# leistung.net
KiCad netlist of a schematic drawn in EAGLE
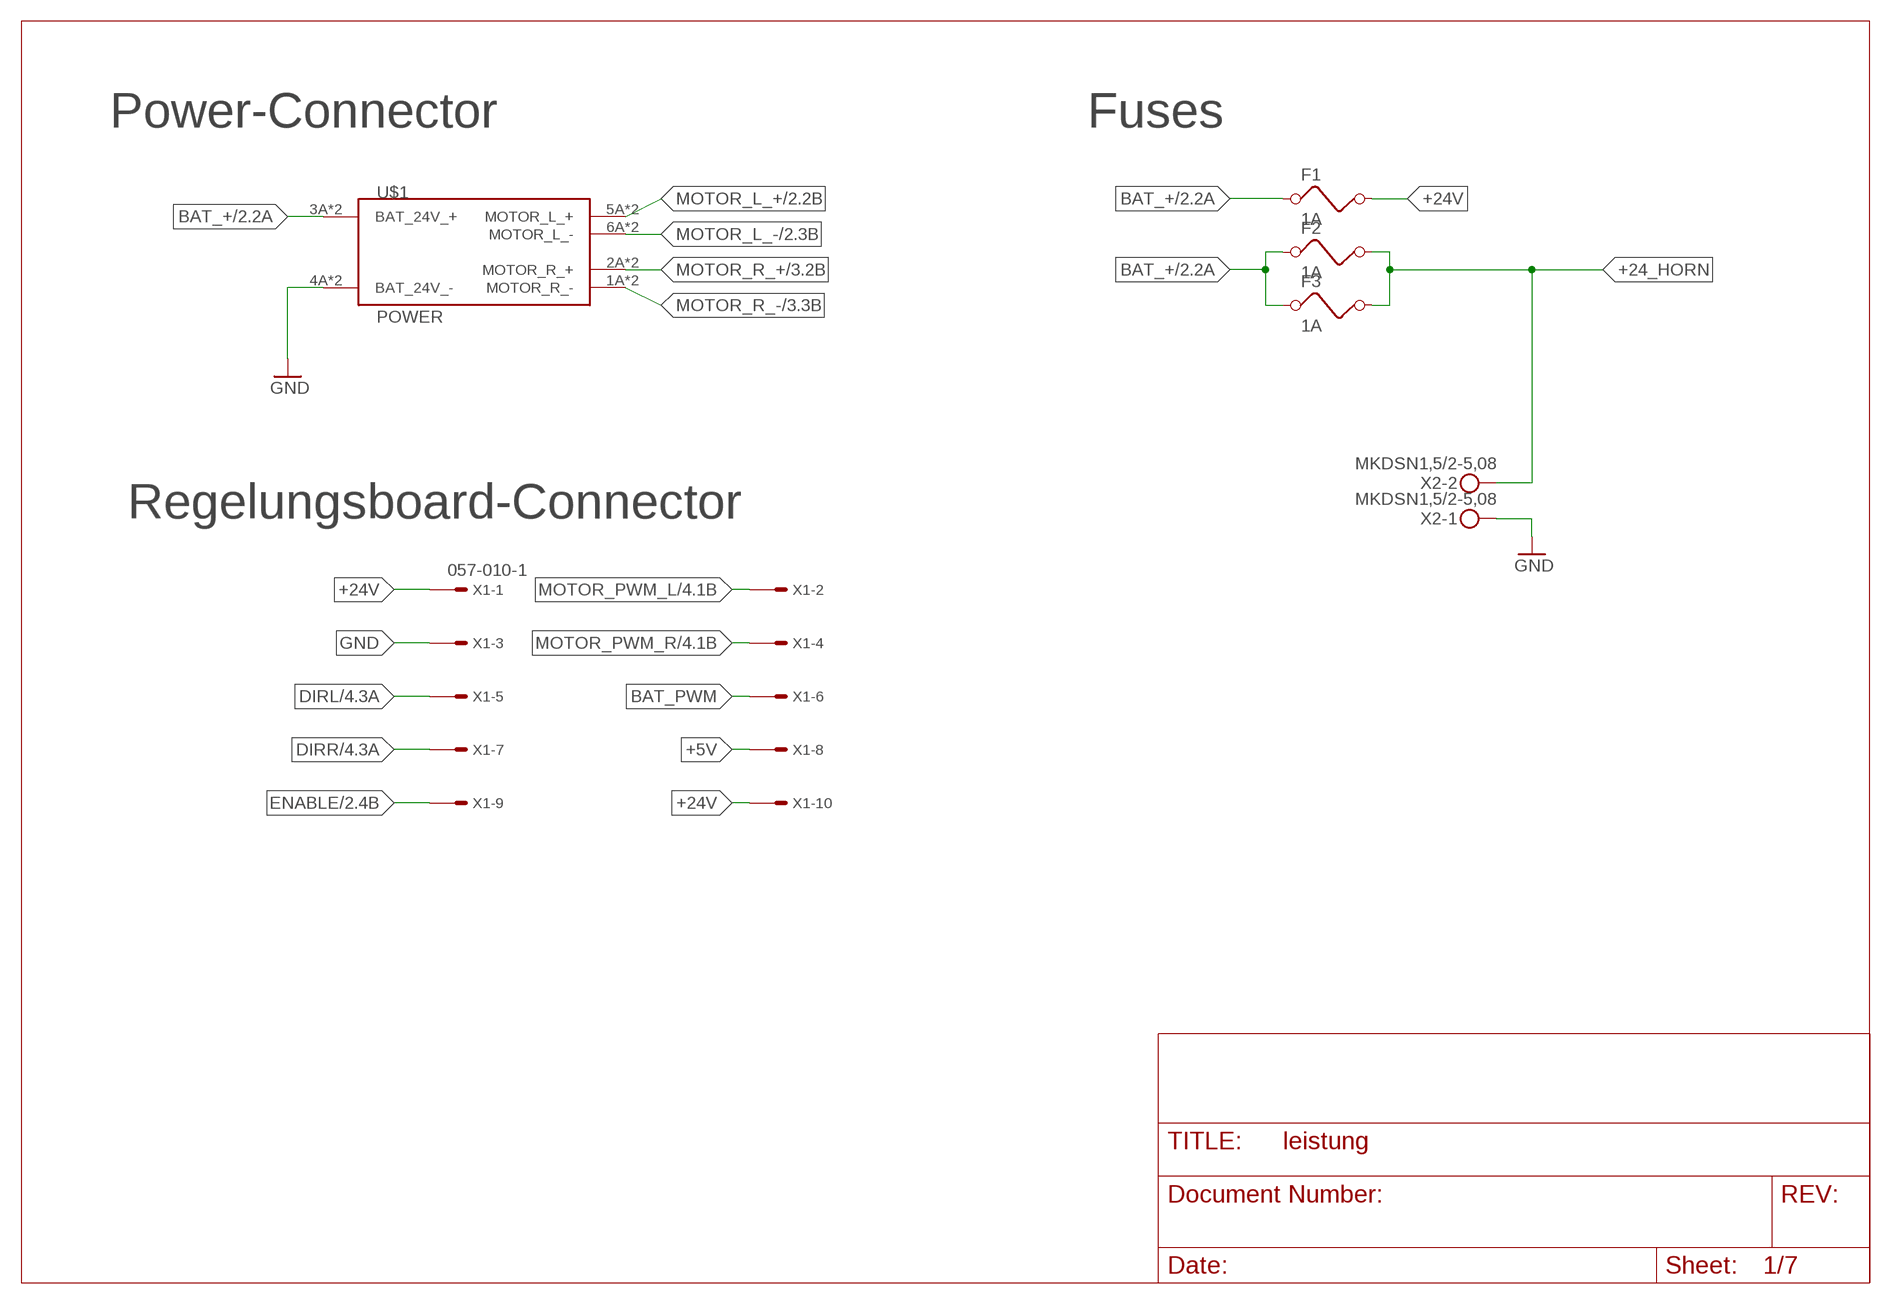
[diagram p0: schematic, sheet 1]
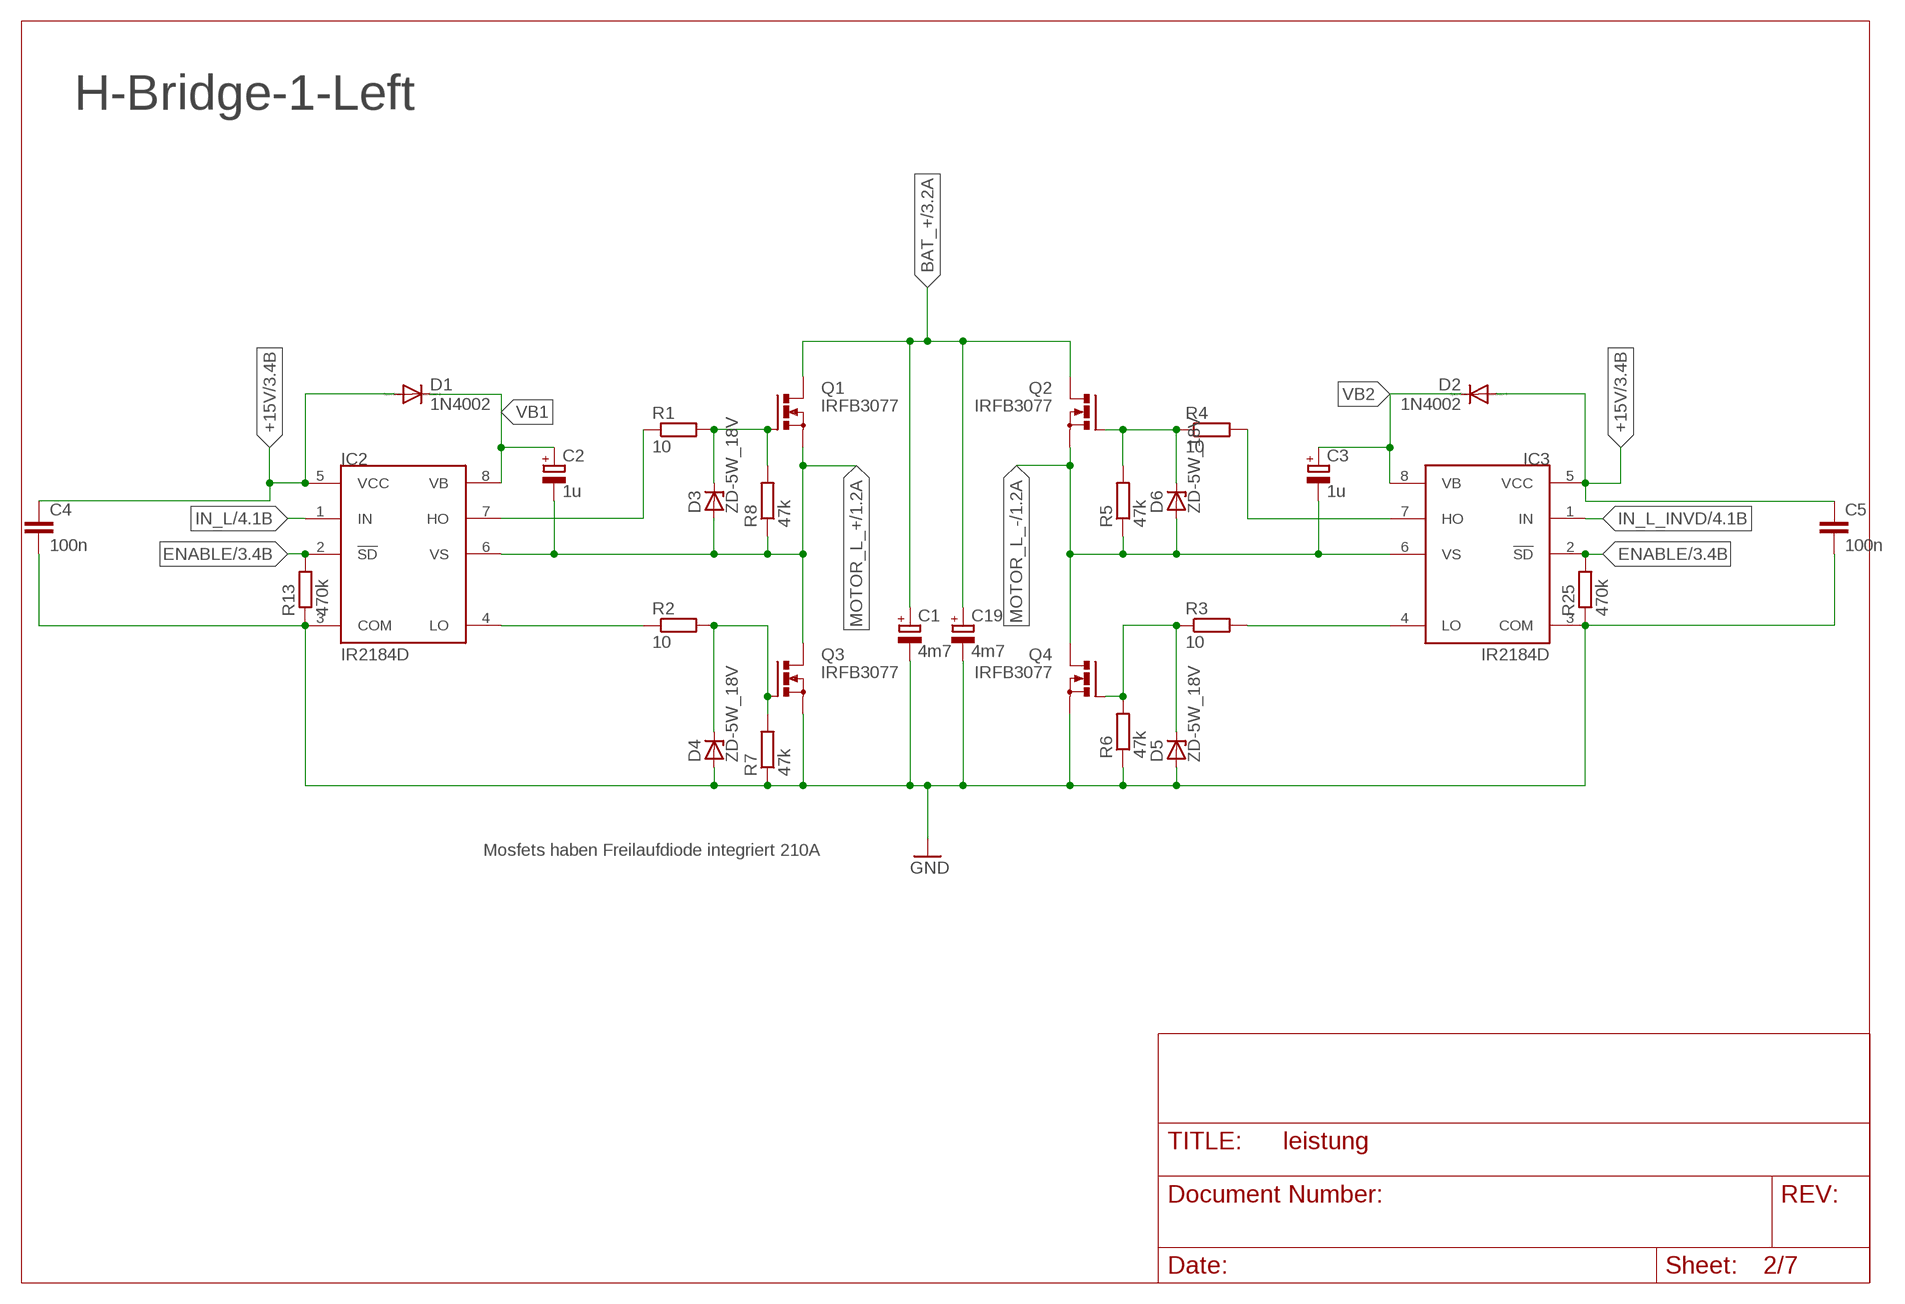
[diagram p1: schematic, sheet 2]
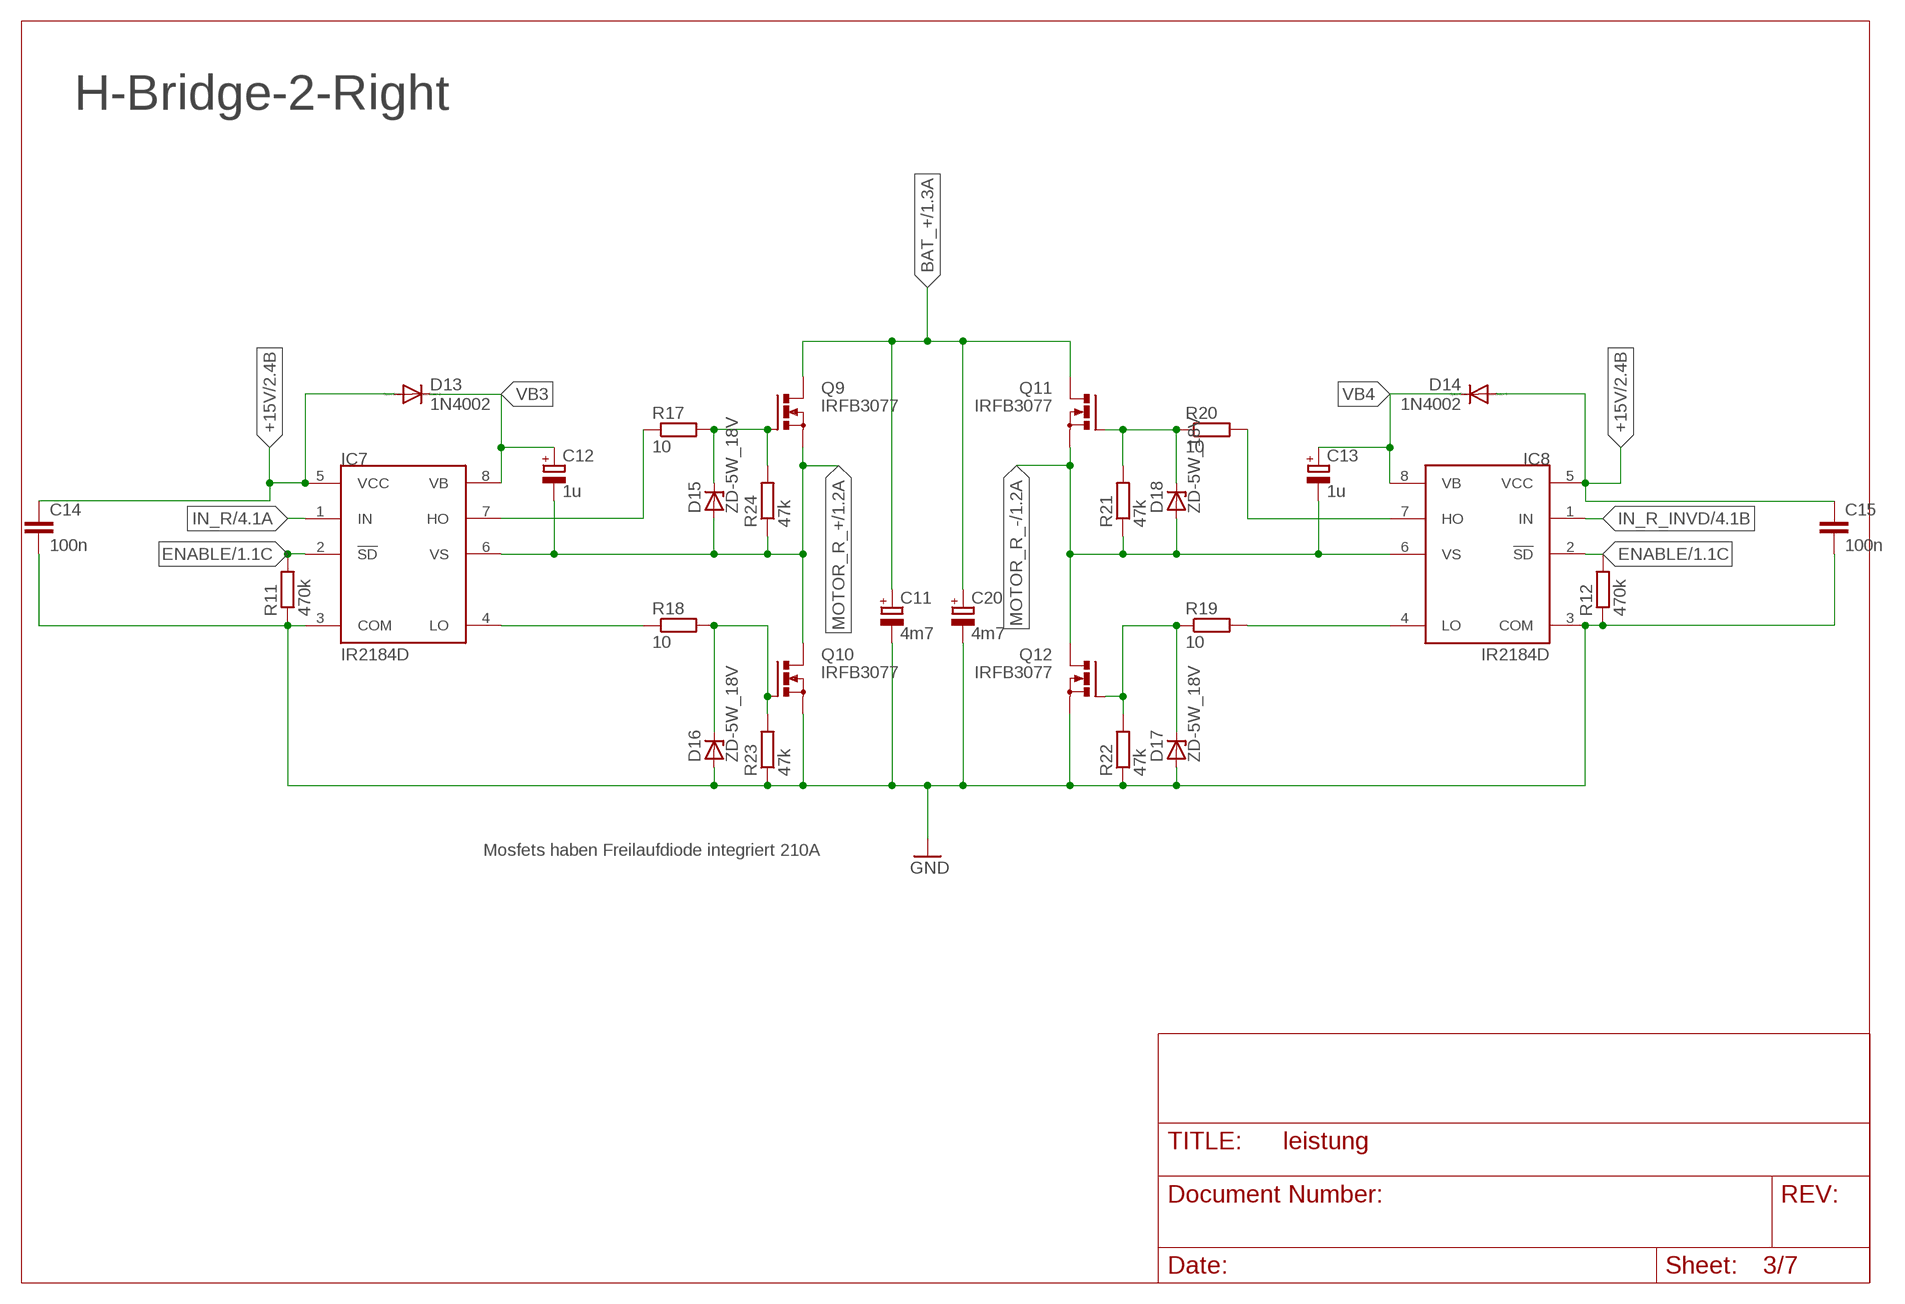
[diagram p2: schematic, sheet 3]
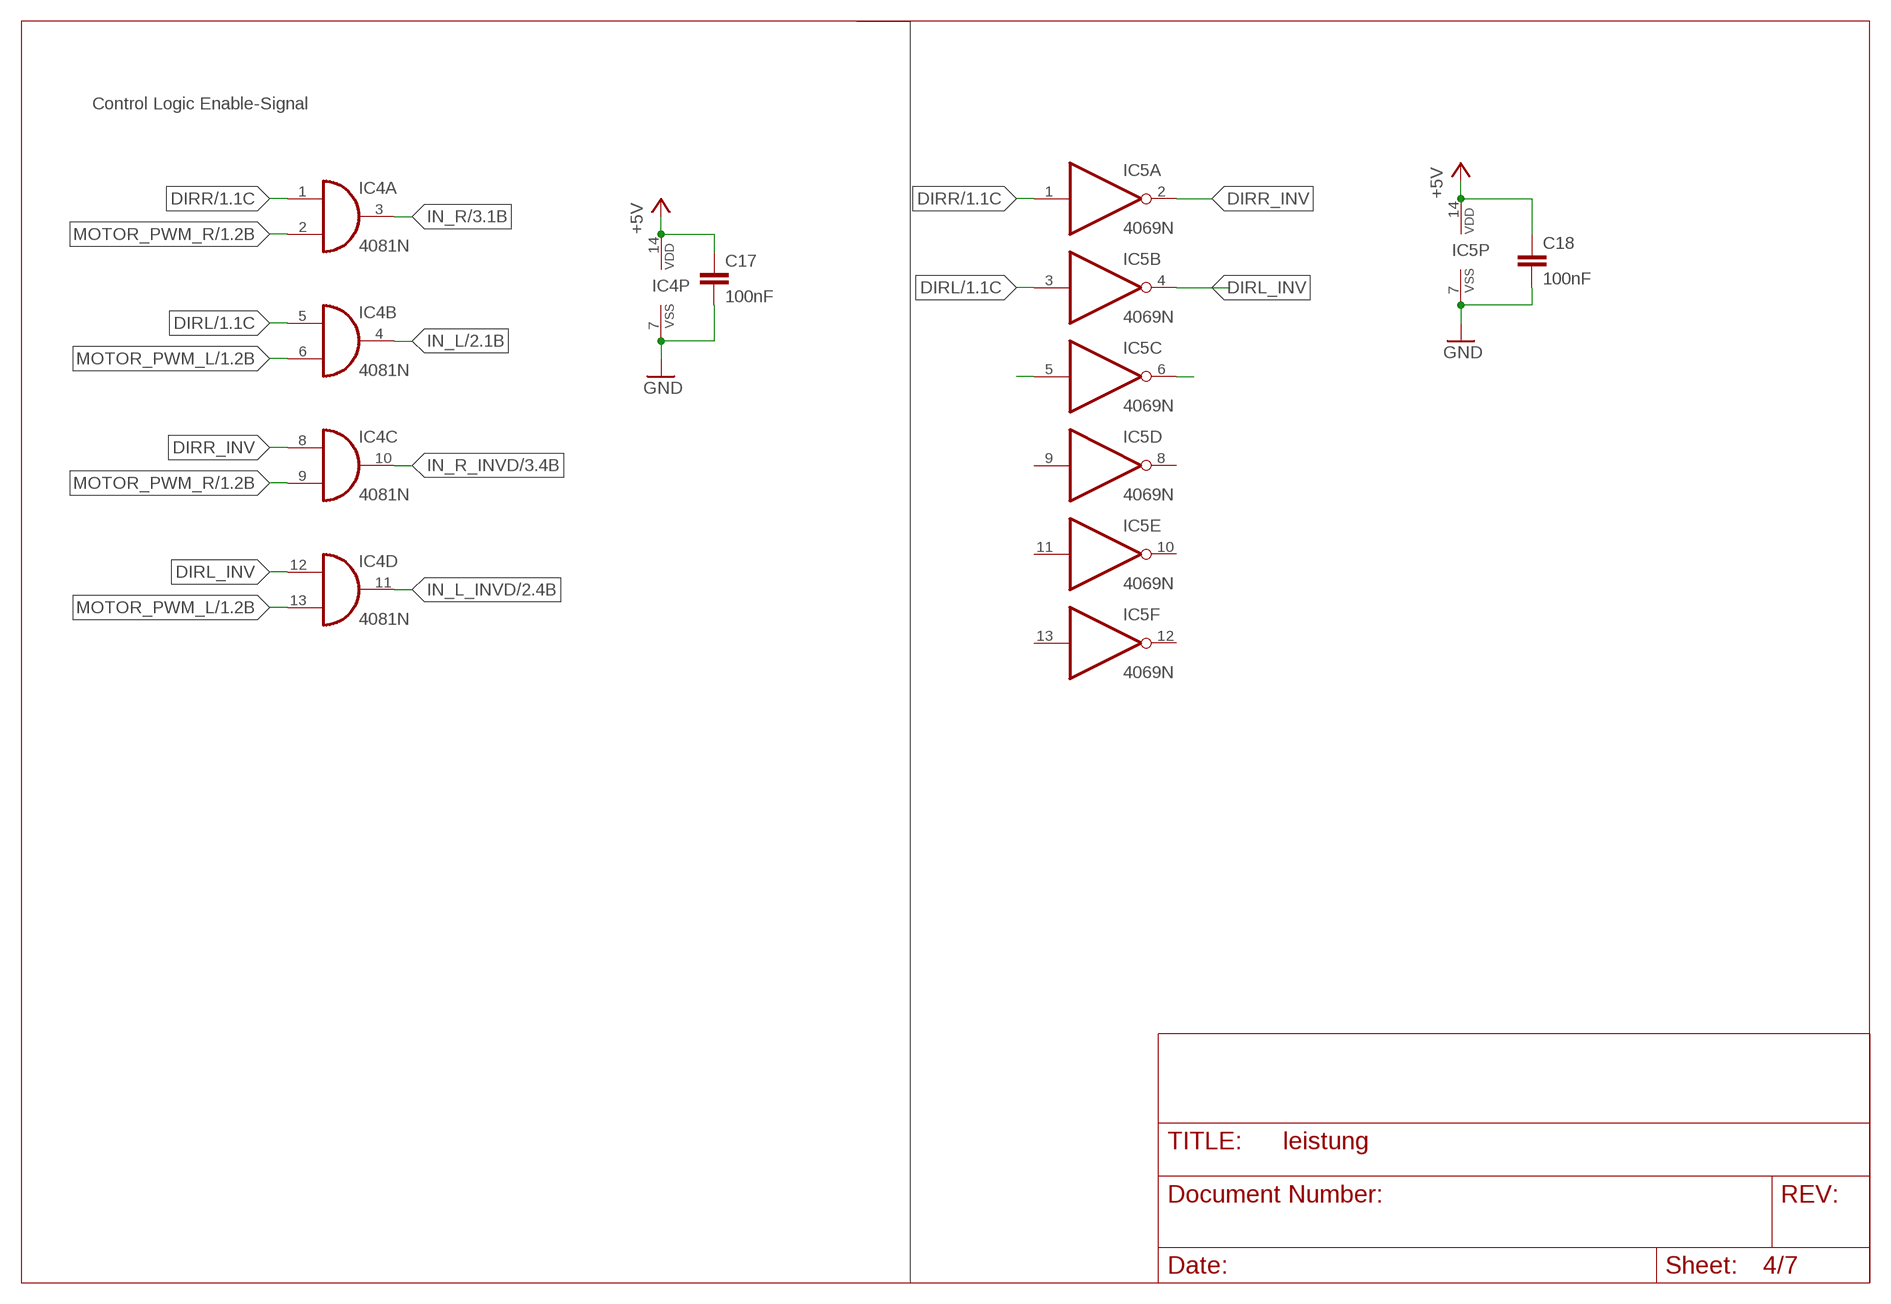
[diagram p3: schematic, sheet 4]
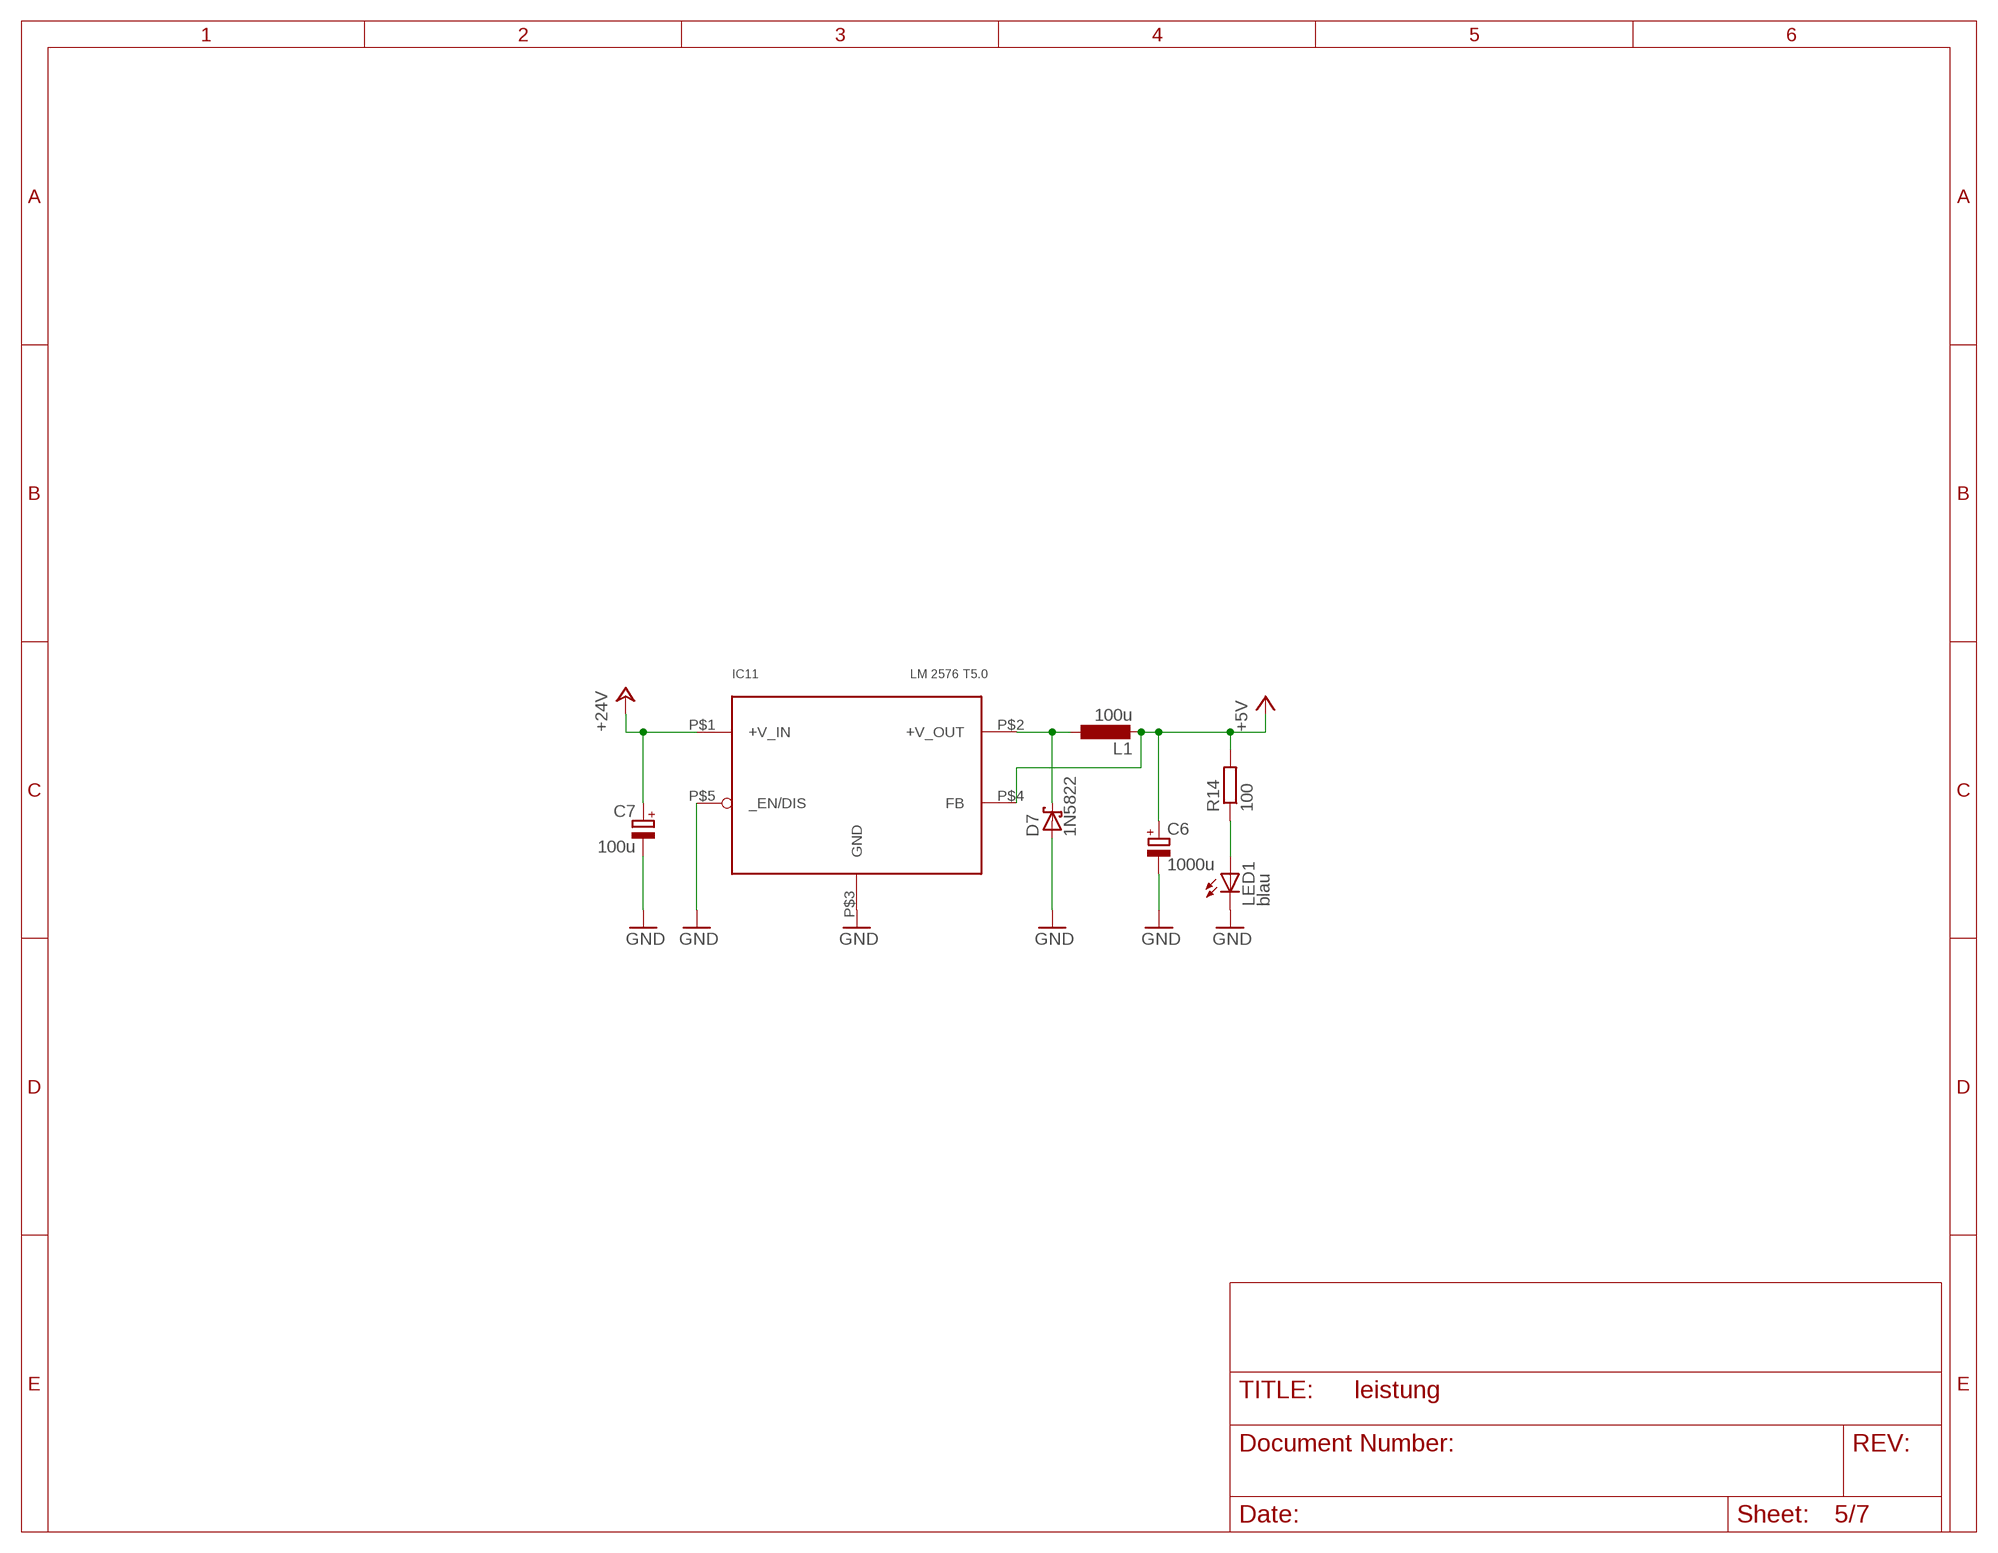
[diagram p4: schematic, sheet 5]
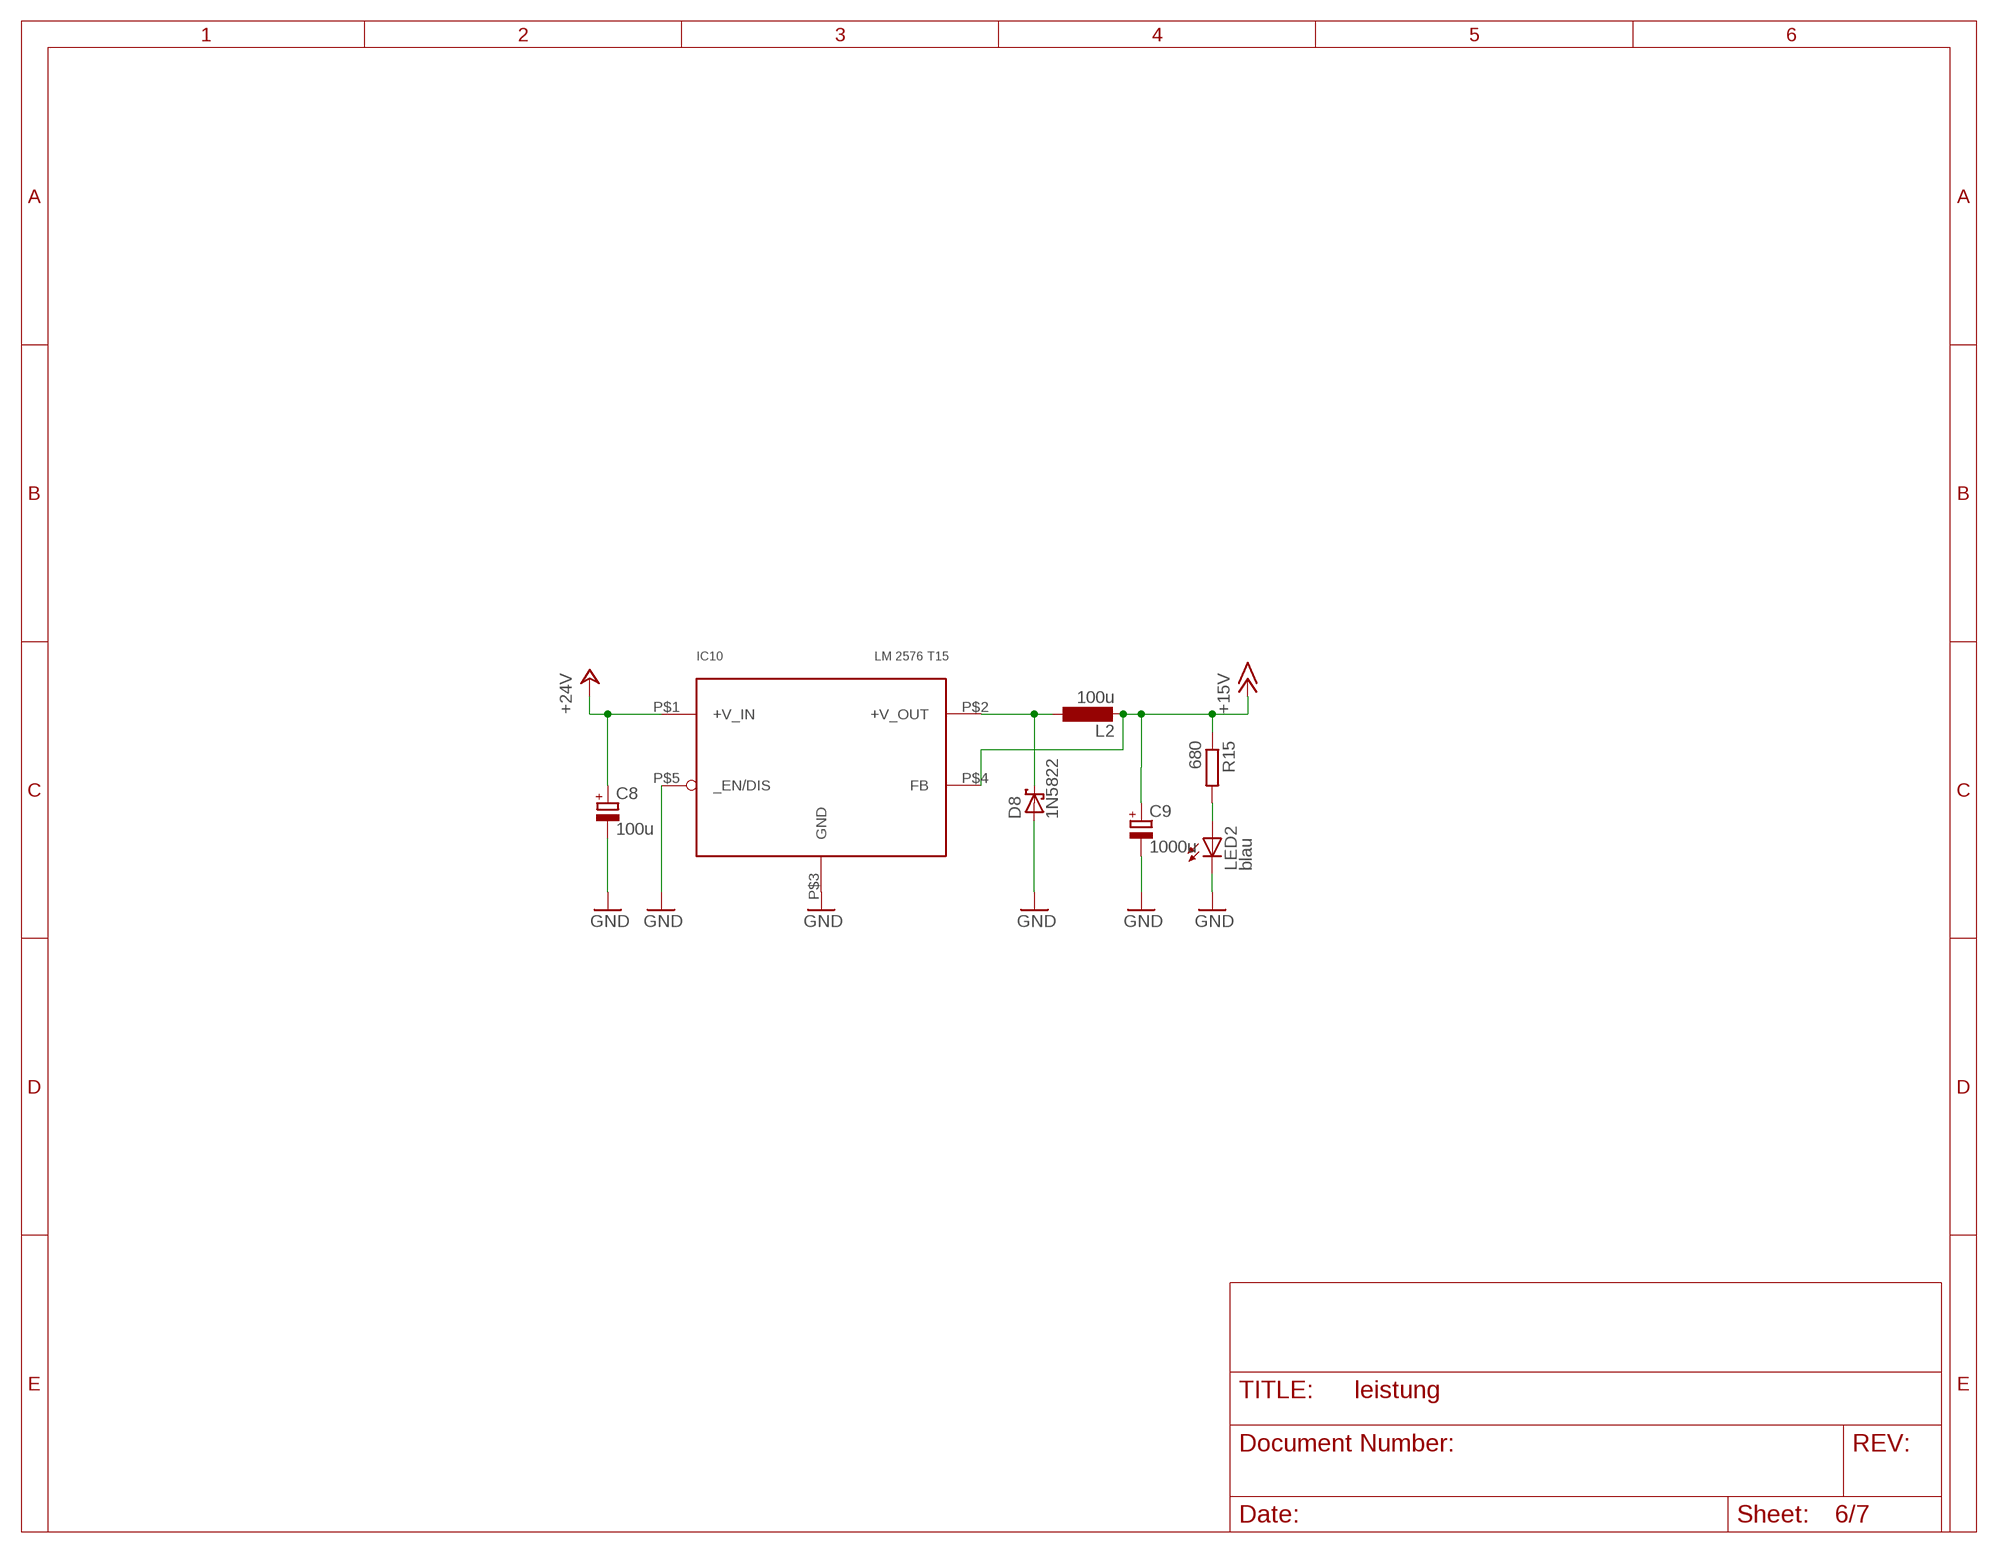
[diagram p5: schematic, sheet 6]
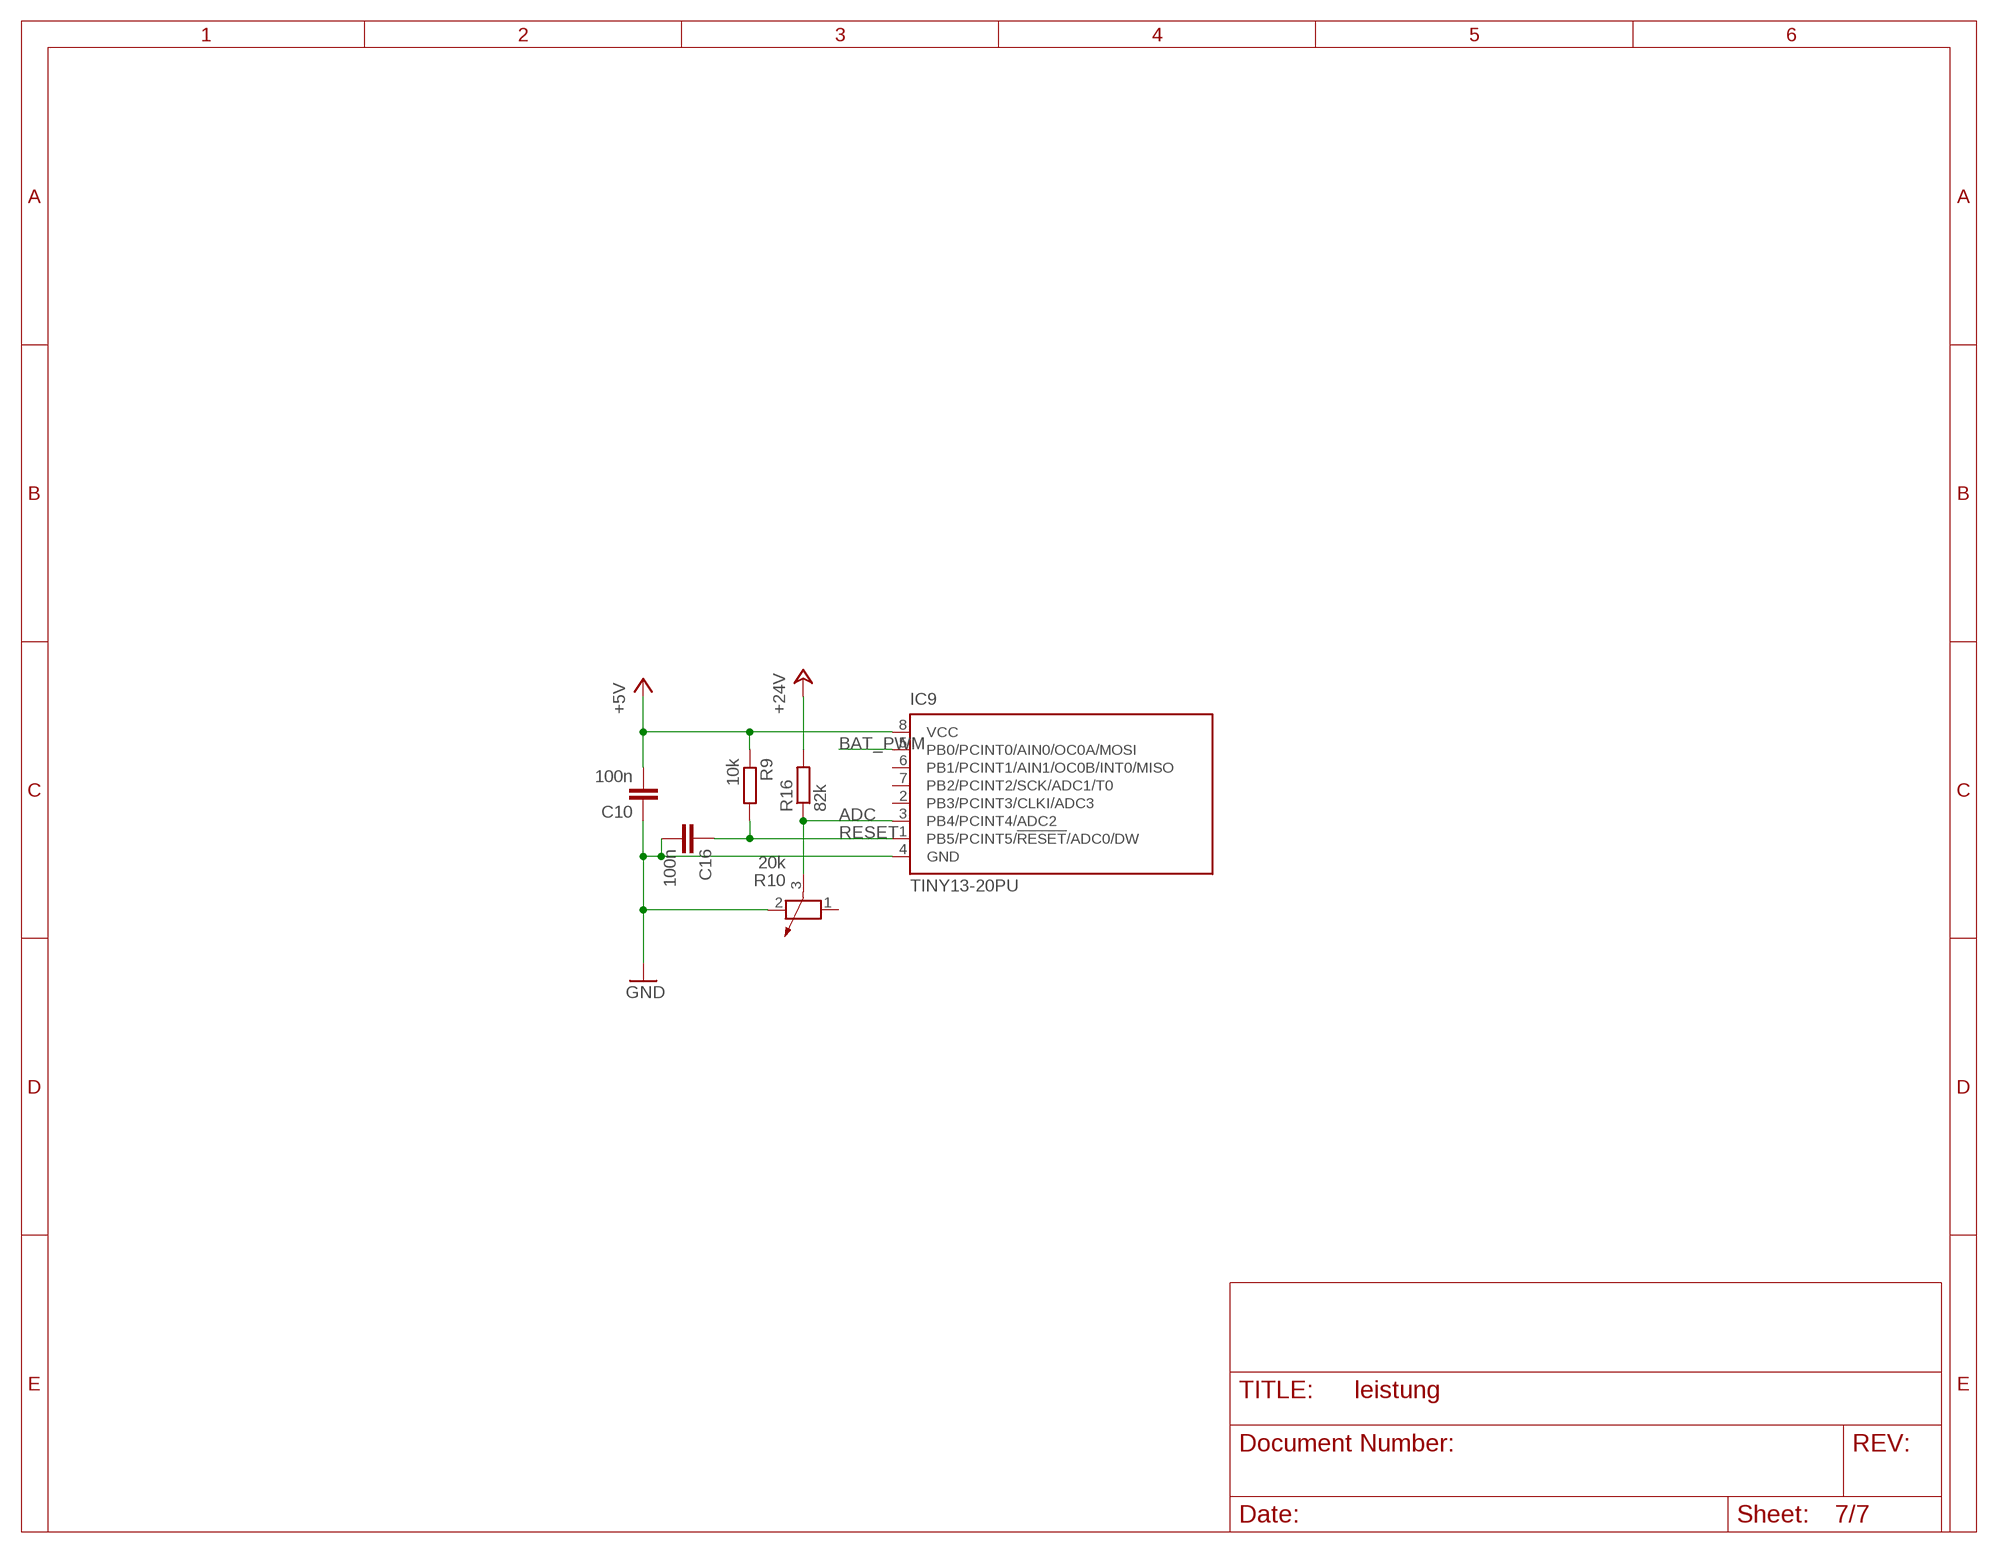
[diagram p6: schematic, sheet 7]

(export (version "E")
  (design (tool "Eeschema 10.0.6"))
  (components
    (comp (ref "F1")
      (value "1A")
      (footprint "eagle-import:FUSE")
      (libsource (lib "eagle-import") (part "FUSE"))
    )
    (comp (ref "F2")
      (value "1A")
      (footprint "eagle-import:FUSE")
      (libsource (lib "eagle-import") (part "FUSE"))
    )
    (comp (ref "F3")
      (value "1A")
      (footprint "eagle-import:FUSE")
      (libsource (lib "eagle-import") (part "FUSE"))
    )
    (comp (ref "U$1")
      (value "POWER")
      (footprint "eagle-import:CON_POWER")
      (libsource (lib "eagle-import") (part "POWER"))
    )
    (comp (ref "X1")
      (value "057-010-1")
      (footprint "eagle-import:057-010-1")
      (libsource (lib "eagle-import") (part "057-010-1"))
    )
    (comp (ref "X2")
      (value "MKDSN1,5/2-5,08")
      (footprint "eagle-import:MKDSN1,5_2-5,08")
      (libsource (lib "eagle-import") (part "MKDSN1,5/2-5,08"))
    )
    (comp (ref "C8")
      (value "100u")
      (footprint "eagle-import:E2,5-7")
      (libsource (lib "eagle-import") (part "CPOL-EUE2.5-7"))
    )
    (comp (ref "C9")
      (value "1000u")
      (footprint "eagle-import:E5-13")
      (libsource (lib "eagle-import") (part "rcl_334_CPOL-EUE5-13"))
    )
    (comp (ref "D8")
      (value "1N5822")
      (footprint "eagle-import:CB429-15")
      (libsource (lib "eagle-import") (part "SCHOTTKY-DIODECB429-15"))
    )
    (comp (ref "IC10")
      (value "LM 2576 T15")
      (footprint "eagle-import:TO220-5_STAGGERED")
      (libsource (lib "eagle-import") (part "LM2576-T05D"))
    )
    (comp (ref "L2")
      (value "100u")
      (footprint "eagle-import:0207_10")
      (libsource (lib "eagle-import") (part "L-EU0207/10"))
    )
    (comp (ref "LED2")
      (value "blau")
      (footprint "eagle-import:LED3MM")
      (libsource (lib "eagle-import") (part "LED3MM"))
    )
    (comp (ref "R15")
      (value "680")
      (footprint "eagle-import:0207_10")
      (libsource (lib "eagle-import") (part "R-EU_0207/10"))
    )
    (comp (ref "C1")
      (value "4m7")
      (footprint "eagle-import:E7,5-18")
      (libsource (lib "eagle-import") (part "rcl_334_CPOL-EUE7.5-18"))
    )
    (comp (ref "C2")
      (value "1u")
      (footprint "eagle-import:E2,5-5")
      (libsource (lib "eagle-import") (part "rcl_334_CPOL-EUE2.5-5"))
    )
    (comp (ref "C3")
      (value "1u")
      (footprint "eagle-import:E2,5-5")
      (libsource (lib "eagle-import") (part "rcl_334_CPOL-EUE2.5-5"))
    )
    (comp (ref "C4")
      (value "100n")
      (footprint "eagle-import:C025-025X050")
      (libsource (lib "eagle-import") (part "rcl_334_C-EU025-025X050"))
    )
    (comp (ref "C5")
      (value "100n")
      (footprint "eagle-import:C025-025X050")
      (libsource (lib "eagle-import") (part "rcl_334_C-EU025-025X050"))
    )
    (comp (ref "C19")
      (value "4m7")
      (footprint "eagle-import:E7,5-18")
      (libsource (lib "eagle-import") (part "rcl_334_CPOL-EUE7.5-18"))
    )
    (comp (ref "D1")
      (value "1N4002")
      (footprint "eagle-import:DO41-10")
      (libsource (lib "eagle-import") (part "1N4004"))
    )
    (comp (ref "D2")
      (value "1N4002")
      (footprint "eagle-import:DO41-10")
      (libsource (lib "eagle-import") (part "1N4004"))
    )
    (comp (ref "D3")
      (value "ZD-5W_18V")
      (footprint "eagle-import:ZDIO-10")
      (libsource (lib "eagle-import") (part "ZENER-DIODEZD-10"))
    )
    (comp (ref "D4")
      (value "ZD-5W_18V")
      (footprint "eagle-import:ZDIO-10")
      (libsource (lib "eagle-import") (part "ZENER-DIODEZD-10"))
    )
    (comp (ref "D5")
      (value "ZD-5W_18V")
      (footprint "eagle-import:ZDIO-10")
      (libsource (lib "eagle-import") (part "ZENER-DIODEZD-10"))
    )
    (comp (ref "D6")
      (value "ZD-5W_18V")
      (footprint "eagle-import:ZDIO-10")
      (libsource (lib "eagle-import") (part "ZENER-DIODEZD-10"))
    )
    (comp (ref "IC2")
      (value "IR2184D")
      (footprint "eagle-import:DIL08")
      (libsource (lib "eagle-import") (part "IR2184D"))
    )
    (comp (ref "IC3")
      (value "IR2184D")
      (footprint "eagle-import:DIL08")
      (libsource (lib "eagle-import") (part "IR2184D"))
    )
    (comp (ref "Q1")
      (value "IRFB3077")
      (footprint "eagle-import:TO220BV")
      (libsource (lib "eagle-import") (part "PMOSFET_NTO220BV"))
    )
    (comp (ref "Q2")
      (value "IRFB3077")
      (footprint "eagle-import:TO220BV")
      (libsource (lib "eagle-import") (part "PMOSFET_NTO220BV"))
    )
    (comp (ref "Q3")
      (value "IRFB3077")
      (footprint "eagle-import:TO220BV")
      (libsource (lib "eagle-import") (part "PMOSFET_NTO220BV"))
    )
    (comp (ref "Q4")
      (value "IRFB3077")
      (footprint "eagle-import:TO220BV")
      (libsource (lib "eagle-import") (part "PMOSFET_NTO220BV"))
    )
    (comp (ref "R1")
      (value "10")
      (footprint "eagle-import:0207_7")
      (libsource (lib "eagle-import") (part "rcl_334_R-EU_0207/7"))
    )
    (comp (ref "R2")
      (value "10")
      (footprint "eagle-import:0207_7")
      (libsource (lib "eagle-import") (part "rcl_334_R-EU_0207/7"))
    )
    (comp (ref "R3")
      (value "10")
      (footprint "eagle-import:0207_7")
      (libsource (lib "eagle-import") (part "rcl_334_R-EU_0207/7"))
    )
    (comp (ref "R4")
      (value "10")
      (footprint "eagle-import:0207_7")
      (libsource (lib "eagle-import") (part "rcl_334_R-EU_0207/7"))
    )
    (comp (ref "R5")
      (value "47k")
      (footprint "eagle-import:0207_7")
      (libsource (lib "eagle-import") (part "rcl_334_R-EU_0207/7"))
    )
    (comp (ref "R6")
      (value "47k")
      (footprint "eagle-import:0207_7")
      (libsource (lib "eagle-import") (part "rcl_334_R-EU_0207/7"))
    )
    (comp (ref "R7")
      (value "47k")
      (footprint "eagle-import:0207_7")
      (libsource (lib "eagle-import") (part "rcl_334_R-EU_0207/7"))
    )
    (comp (ref "R8")
      (value "47k")
      (footprint "eagle-import:0207_7")
      (libsource (lib "eagle-import") (part "rcl_334_R-EU_0207/7"))
    )
    (comp (ref "R13")
      (value "470k")
      (footprint "eagle-import:0207_7")
      (libsource (lib "eagle-import") (part "rcl_334_R-EU_0207/7"))
    )
    (comp (ref "R25")
      (value "470k")
      (footprint "eagle-import:0207_7")
      (libsource (lib "eagle-import") (part "rcl_334_R-EU_0207/7"))
    )
    (comp (ref "C17")
      (value "100nF")
      (footprint "eagle-import:C025-025X050")
      (libsource (lib "eagle-import") (part "rcl_334_C-EU025-025X050"))
    )
    (comp (ref "C18")
      (value "100nF")
      (footprint "eagle-import:C025-025X050")
      (libsource (lib "eagle-import") (part "rcl_334_C-EU025-025X050"))
    )
    (comp (ref "IC4")
      (value "4081N")
      (footprint "eagle-import:DIL14")
      (libsource (lib "eagle-import") (part "4081N"))
    )
    (comp (ref "IC5")
      (value "4069N")
      (footprint "eagle-import:DIL14")
      (libsource (lib "eagle-import") (part "4069N"))
    )
    (comp (ref "C10")
      (value "100n")
      (footprint "eagle-import:C025-025X050")
      (libsource (lib "eagle-import") (part "C-EU025-025X050"))
    )
    (comp (ref "C16")
      (value "100n")
      (footprint "eagle-import:C025-025X050")
      (libsource (lib "eagle-import") (part "C-EU025-025X050"))
    )
    (comp (ref "IC9")
      (value "TINY13-20PU")
      (footprint "eagle-import:DIL08")
      (fields (field (name "MPN") "ATTINY13-20PU"))
      (libsource (lib "eagle-import") (part "TINY13PU-20"))
    )
    (comp (ref "R9")
      (value "10k")
      (footprint "eagle-import:0207_10")
      (libsource (lib "eagle-import") (part "R-EU_0207/10"))
    )
    (comp (ref "R10")
      (value "20k")
      (footprint "eagle-import:PT-10")
      (libsource (lib "eagle-import") (part "POTENTIOMETER_PT-10"))
    )
    (comp (ref "R16")
      (value "82k")
      (footprint "eagle-import:0207_10")
      (libsource (lib "eagle-import") (part "R-EU_0207/10"))
    )
    (comp (ref "C6")
      (value "1000u")
      (footprint "eagle-import:E5-13")
      (libsource (lib "eagle-import") (part "rcl_334_CPOL-EUE5-13"))
    )
    (comp (ref "C7")
      (value "100u")
      (footprint "eagle-import:E2,5-4R")
      (libsource (lib "eagle-import") (part "CPOL-EUE2.5-5V"))
    )
    (comp (ref "D7")
      (value "1N5822")
      (footprint "eagle-import:CB417-15")
      (libsource (lib "eagle-import") (part "SCHOTTKY-DIODECB417-15"))
    )
    (comp (ref "IC11")
      (value "LM 2576 T5.0")
      (footprint "eagle-import:TO220-5_STAGGERED")
      (libsource (lib "eagle-import") (part "LM2576-T05D"))
    )
    (comp (ref "L1")
      (value "100u")
      (footprint "eagle-import:0207_10")
      (libsource (lib "eagle-import") (part "L-EU0207/10"))
    )
    (comp (ref "LED1")
      (value "blau")
      (footprint "eagle-import:LED3MM")
      (libsource (lib "eagle-import") (part "LED3MM"))
    )
    (comp (ref "R14")
      (value "100")
      (footprint "eagle-import:0207_10")
      (libsource (lib "eagle-import") (part "R-EU_0207/10"))
    )
    (comp (ref "C11")
      (value "4m7")
      (footprint "eagle-import:E7,5-18")
      (libsource (lib "eagle-import") (part "rcl_334_CPOL-EUE7.5-18"))
    )
    (comp (ref "C12")
      (value "1u")
      (footprint "eagle-import:E2,5-5")
      (libsource (lib "eagle-import") (part "rcl_334_CPOL-EUE2.5-5"))
    )
    (comp (ref "C13")
      (value "1u")
      (footprint "eagle-import:E2,5-5")
      (libsource (lib "eagle-import") (part "rcl_334_CPOL-EUE2.5-5"))
    )
    (comp (ref "C14")
      (value "100n")
      (footprint "eagle-import:C025-025X050")
      (libsource (lib "eagle-import") (part "rcl_334_C-EU025-025X050"))
    )
    (comp (ref "C15")
      (value "100n")
      (footprint "eagle-import:C025-025X050")
      (libsource (lib "eagle-import") (part "rcl_334_C-EU025-025X050"))
    )
    (comp (ref "C20")
      (value "4m7")
      (footprint "eagle-import:E7,5-18")
      (libsource (lib "eagle-import") (part "rcl_334_CPOL-EUE7.5-18"))
    )
    (comp (ref "D13")
      (value "1N4002")
      (footprint "eagle-import:DO41-10")
      (libsource (lib "eagle-import") (part "1N4004"))
    )
    (comp (ref "D14")
      (value "1N4002")
      (footprint "eagle-import:DO41-10")
      (libsource (lib "eagle-import") (part "1N4004"))
    )
    (comp (ref "D15")
      (value "ZD-5W_18V")
      (footprint "eagle-import:ZDIO-10")
      (libsource (lib "eagle-import") (part "ZENER-DIODEZD-10"))
    )
    (comp (ref "D16")
      (value "ZD-5W_18V")
      (footprint "eagle-import:ZDIO-10")
      (libsource (lib "eagle-import") (part "ZENER-DIODEZD-10"))
    )
    (comp (ref "D17")
      (value "ZD-5W_18V")
      (footprint "eagle-import:ZDIO-10")
      (libsource (lib "eagle-import") (part "ZENER-DIODEZD-10"))
    )
    (comp (ref "D18")
      (value "ZD-5W_18V")
      (footprint "eagle-import:ZDIO-10")
      (libsource (lib "eagle-import") (part "ZENER-DIODEZD-10"))
    )
    (comp (ref "IC7")
      (value "IR2184D")
      (footprint "eagle-import:DIL08")
      (libsource (lib "eagle-import") (part "IR2184D"))
    )
    (comp (ref "IC8")
      (value "IR2184D")
      (footprint "eagle-import:DIL08")
      (libsource (lib "eagle-import") (part "IR2184D"))
    )
    (comp (ref "Q9")
      (value "IRFB3077")
      (footprint "eagle-import:TO220BV")
      (libsource (lib "eagle-import") (part "PMOSFET_NTO220BV"))
    )
    (comp (ref "Q10")
      (value "IRFB3077")
      (footprint "eagle-import:TO220BV")
      (libsource (lib "eagle-import") (part "PMOSFET_NTO220BV"))
    )
    (comp (ref "Q11")
      (value "IRFB3077")
      (footprint "eagle-import:TO220BV")
      (libsource (lib "eagle-import") (part "PMOSFET_NTO220BV"))
    )
    (comp (ref "Q12")
      (value "IRFB3077")
      (footprint "eagle-import:TO220BV")
      (libsource (lib "eagle-import") (part "PMOSFET_NTO220BV"))
    )
    (comp (ref "R11")
      (value "470k")
      (footprint "eagle-import:0207_7")
      (libsource (lib "eagle-import") (part "rcl_334_R-EU_0207/7"))
    )
    (comp (ref "R12")
      (value "470k")
      (footprint "eagle-import:0207_7")
      (libsource (lib "eagle-import") (part "rcl_334_R-EU_0207/7"))
    )
    (comp (ref "R17")
      (value "10")
      (footprint "eagle-import:0207_7")
      (libsource (lib "eagle-import") (part "rcl_334_R-EU_0207/7"))
    )
    (comp (ref "R18")
      (value "10")
      (footprint "eagle-import:0207_7")
      (libsource (lib "eagle-import") (part "rcl_334_R-EU_0207/7"))
    )
    (comp (ref "R19")
      (value "10")
      (footprint "eagle-import:0207_7")
      (libsource (lib "eagle-import") (part "rcl_334_R-EU_0207/7"))
    )
    (comp (ref "R20")
      (value "10")
      (footprint "eagle-import:0207_7")
      (libsource (lib "eagle-import") (part "rcl_334_R-EU_0207/7"))
    )
    (comp (ref "R21")
      (value "47k")
      (footprint "eagle-import:0207_7")
      (libsource (lib "eagle-import") (part "rcl_334_R-EU_0207/7"))
    )
    (comp (ref "R22")
      (value "47k")
      (footprint "eagle-import:0207_7")
      (libsource (lib "eagle-import") (part "rcl_334_R-EU_0207/7"))
    )
    (comp (ref "R23")
      (value "47k")
      (footprint "eagle-import:0207_7")
      (libsource (lib "eagle-import") (part "rcl_334_R-EU_0207/7"))
    )
    (comp (ref "R24")
      (value "47k")
      (footprint "eagle-import:0207_7")
      (libsource (lib "eagle-import") (part "rcl_334_R-EU_0207/7"))
    )
  )
  (nets
    (net (code "1") (name "+5V") (class "Default")
      (node (ref "C10") (pin "2") (pinfunction "2_2") (pintype "passive"))
      (node (ref "C17") (pin "1") (pinfunction "1_1") (pintype "passive"))
      (node (ref "C18") (pin "1") (pinfunction "1_1") (pintype "passive"))
      (node (ref "C6") (pin "+") (pinfunction "+_+") (pintype "passive"))
      (node (ref "IC11") (pin "P$4") (pinfunction "FB_P$4") (pintype "input"))
      (node (ref "IC4") (pin "14") (pinfunction "VDD_14") (pintype "power_in"))
      (node (ref "IC5") (pin "14") (pinfunction "VDD_14") (pintype "power_in"))
      (node (ref "IC9") (pin "8") (pinfunction "VCC_8") (pintype "power_in"))
      (node (ref "L1") (pin "2") (pinfunction "2_2") (pintype "passive"))
      (node (ref "R14") (pin "2") (pinfunction "2_2") (pintype "passive"))
      (node (ref "R9") (pin "1") (pinfunction "1_1") (pintype "passive"))
      (node (ref "X1") (pin "8") (pinfunction "S_8") (pintype "passive"))
    )
    (net (code "2") (name "+15V") (class "Default")
      (node (ref "C14") (pin "1") (pinfunction "1_1") (pintype "passive"))
      (node (ref "C15") (pin "1") (pinfunction "1_1") (pintype "passive"))
      (node (ref "C4") (pin "1") (pinfunction "1_1") (pintype "passive"))
      (node (ref "C5") (pin "1") (pinfunction "1_1") (pintype "passive"))
      (node (ref "C9") (pin "+") (pinfunction "+_+") (pintype "passive"))
      (node (ref "D1") (pin "A") (pinfunction "A_A") (pintype "passive"))
      (node (ref "D13") (pin "A") (pinfunction "A_A") (pintype "passive"))
      (node (ref "D14") (pin "A") (pinfunction "A_A") (pintype "passive"))
      (node (ref "D2") (pin "A") (pinfunction "A_A") (pintype "passive"))
      (node (ref "IC10") (pin "P$4") (pinfunction "FB_P$4") (pintype "input"))
      (node (ref "IC2") (pin "5") (pinfunction "VCC_5") (pintype "power_in"))
      (node (ref "IC3") (pin "5") (pinfunction "VCC_5") (pintype "power_in"))
      (node (ref "IC7") (pin "5") (pinfunction "VCC_5") (pintype "power_in"))
      (node (ref "IC8") (pin "5") (pinfunction "VCC_5") (pintype "power_in"))
      (node (ref "L2") (pin "2") (pinfunction "2_2") (pintype "passive"))
      (node (ref "R15") (pin "1") (pinfunction "1_1") (pintype "passive"))
    )
    (net (code "3") (name "+24V") (class "Default")
      (node (ref "C7") (pin "+") (pinfunction "+_+") (pintype "passive"))
      (node (ref "C8") (pin "+") (pinfunction "+_+") (pintype "passive"))
      (node (ref "F1") (pin "2") (pinfunction "2_2") (pintype "passive"))
      (node (ref "IC10") (pin "P$1") (pinfunction "+V_IN_P$1") (pintype "input"))
      (node (ref "IC11") (pin "P$1") (pinfunction "+V_IN_P$1") (pintype "input"))
      (node (ref "R16") (pin "2") (pinfunction "2_2") (pintype "passive"))
      (node (ref "X1") (pin "1") (pinfunction "S_1") (pintype "passive"))
      (node (ref "X1") (pin "10") (pinfunction "S_10") (pintype "passive"))
    )
    (net (code "4") (name "+24_HORN") (class "Default")
      (node (ref "F2") (pin "2") (pinfunction "2_2") (pintype "passive"))
      (node (ref "F3") (pin "2") (pinfunction "2_2") (pintype "passive"))
      (node (ref "X2") (pin "2") (pinfunction "KL_2") (pintype "passive"))
    )
    (net (code "5") (name "ADC") (class "Default")
      (node (ref "IC9") (pin "3") (pinfunction "PB4/PCINT4/ADC2_3") (pintype "bidirectional"))
      (node (ref "R10") (pin "3") (pinfunction "3_3") (pintype "passive"))
      (node (ref "R16") (pin "1") (pinfunction "1_1") (pintype "passive"))
    )
    (net (code "6") (name "BAT_+") (class "Default")
      (node (ref "C1") (pin "+") (pinfunction "+_+") (pintype "passive"))
      (node (ref "C11") (pin "+") (pinfunction "+_+") (pintype "passive"))
      (node (ref "C19") (pin "+") (pinfunction "+_+") (pintype "passive"))
      (node (ref "C20") (pin "+") (pinfunction "+_+") (pintype "passive"))
      (node (ref "F1") (pin "1") (pinfunction "1_1") (pintype "passive"))
      (node (ref "F2") (pin "1") (pinfunction "1_1") (pintype "passive"))
      (node (ref "F3") (pin "1") (pinfunction "1_1") (pintype "passive"))
      (node (ref "Q1") (pin "D") (pinfunction "D_D") (pintype "passive"))
      (node (ref "Q11") (pin "D") (pinfunction "D_D") (pintype "passive"))
      (node (ref "Q2") (pin "D") (pinfunction "D_D") (pintype "passive"))
      (node (ref "Q9") (pin "D") (pinfunction "D_D") (pintype "passive"))
      (node (ref "U$1") (pin "3A") (pinfunction "BAT_24V_+_3A") (pintype "power_in"))
      (node (ref "U$1") (pin "3B") (pinfunction "BAT_24V_+_3B") (pintype "power_in"))
    )
    (net (code "7") (name "BAT_PWM") (class "Default")
      (node (ref "IC9") (pin "5") (pinfunction "PB0/PCINT0/AIN0/OC0A/MOSI_5") (pintype "bidirectional"))
      (node (ref "X1") (pin "6") (pinfunction "S_6") (pintype "passive"))
    )
    (net (code "8") (name "DIRL") (class "Default")
      (node (ref "IC4") (pin "5") (pinfunction "I0_5") (pintype "input"))
      (node (ref "IC5") (pin "3") (pinfunction "I_3") (pintype "input"))
      (node (ref "X1") (pin "5") (pinfunction "S_5") (pintype "passive"))
    )
    (net (code "9") (name "DIRL_INV") (class "Default")
      (node (ref "IC4") (pin "12") (pinfunction "I0_12") (pintype "input"))
      (node (ref "IC5") (pin "4") (pinfunction "O_4") (pintype "output"))
    )
    (net (code "10") (name "DIRR") (class "Default")
      (node (ref "IC4") (pin "1") (pinfunction "I0_1") (pintype "input"))
      (node (ref "IC5") (pin "1") (pinfunction "I_1") (pintype "input"))
      (node (ref "X1") (pin "7") (pinfunction "S_7") (pintype "passive"))
    )
    (net (code "11") (name "DIRR_INV") (class "Default")
      (node (ref "IC4") (pin "8") (pinfunction "I0_8") (pintype "input"))
      (node (ref "IC5") (pin "2") (pinfunction "O_2") (pintype "output"))
    )
    (net (code "12") (name "ENABLE") (class "Default")
      (node (ref "IC2") (pin "2") (pinfunction "~{SD}_2") (pintype "input"))
      (node (ref "IC3") (pin "2") (pinfunction "~{SD}_2") (pintype "input"))
      (node (ref "IC7") (pin "2") (pinfunction "~{SD}_2") (pintype "input"))
      (node (ref "IC8") (pin "2") (pinfunction "~{SD}_2") (pintype "input"))
      (node (ref "R11") (pin "2") (pinfunction "2_2") (pintype "passive"))
      (node (ref "R12") (pin "2") (pinfunction "2_2") (pintype "passive"))
      (node (ref "R13") (pin "2") (pinfunction "2_2") (pintype "passive"))
      (node (ref "R25") (pin "2") (pinfunction "2_2") (pintype "passive"))
      (node (ref "X1") (pin "9") (pinfunction "S_9") (pintype "passive"))
    )
    (net (code "13") (name "GND") (class "Default")
      (node (ref "C1") (pin "-") (pinfunction "-_-") (pintype "passive"))
      (node (ref "C10") (pin "1") (pinfunction "1_1") (pintype "passive"))
      (node (ref "C11") (pin "-") (pinfunction "-_-") (pintype "passive"))
      (node (ref "C14") (pin "2") (pinfunction "2_2") (pintype "passive"))
      (node (ref "C15") (pin "2") (pinfunction "2_2") (pintype "passive"))
      (node (ref "C16") (pin "2") (pinfunction "2_2") (pintype "passive"))
      (node (ref "C17") (pin "2") (pinfunction "2_2") (pintype "passive"))
      (node (ref "C18") (pin "2") (pinfunction "2_2") (pintype "passive"))
      (node (ref "C19") (pin "-") (pinfunction "-_-") (pintype "passive"))
      (node (ref "C20") (pin "-") (pinfunction "-_-") (pintype "passive"))
      (node (ref "C4") (pin "2") (pinfunction "2_2") (pintype "passive"))
      (node (ref "C5") (pin "2") (pinfunction "2_2") (pintype "passive"))
      (node (ref "C6") (pin "-") (pinfunction "-_-") (pintype "passive"))
      (node (ref "C7") (pin "-") (pinfunction "-_-") (pintype "passive"))
      (node (ref "C8") (pin "-") (pinfunction "-_-") (pintype "passive"))
      (node (ref "C9") (pin "-") (pinfunction "-_-") (pintype "passive"))
      (node (ref "D16") (pin "A") (pinfunction "A_A") (pintype "passive"))
      (node (ref "D17") (pin "A") (pinfunction "A_A") (pintype "passive"))
      (node (ref "D4") (pin "A") (pinfunction "A_A") (pintype "passive"))
      (node (ref "D5") (pin "A") (pinfunction "A_A") (pintype "passive"))
      (node (ref "D7") (pin "A") (pinfunction "A_A") (pintype "passive"))
      (node (ref "D8") (pin "A") (pinfunction "A_A") (pintype "passive"))
      (node (ref "IC10") (pin "P$3") (pinfunction "GND_P$3") (pintype "power_in"))
      (node (ref "IC10") (pin "P$5") (pinfunction "_EN/DIS_P$5") (pintype "input"))
      (node (ref "IC11") (pin "P$3") (pinfunction "GND_P$3") (pintype "power_in"))
      (node (ref "IC11") (pin "P$5") (pinfunction "_EN/DIS_P$5") (pintype "input"))
      (node (ref "IC2") (pin "3") (pinfunction "COM_3") (pintype "power_in"))
      (node (ref "IC3") (pin "3") (pinfunction "COM_3") (pintype "power_in"))
      (node (ref "IC4") (pin "7") (pinfunction "VSS_7") (pintype "power_in"))
      (node (ref "IC5") (pin "7") (pinfunction "VSS_7") (pintype "power_in"))
      (node (ref "IC7") (pin "3") (pinfunction "COM_3") (pintype "power_in"))
      (node (ref "IC8") (pin "3") (pinfunction "COM_3") (pintype "power_in"))
      (node (ref "IC9") (pin "4") (pinfunction "GND_4") (pintype "power_in"))
      (node (ref "LED1") (pin "K") (pinfunction "C_K") (pintype "passive"))
      (node (ref "LED2") (pin "K") (pinfunction "C_K") (pintype "passive"))
      (node (ref "Q10") (pin "S") (pinfunction "S_S") (pintype "passive"))
      (node (ref "Q12") (pin "S") (pinfunction "S_S") (pintype "passive"))
      (node (ref "Q3") (pin "S") (pinfunction "S_S") (pintype "passive"))
      (node (ref "Q4") (pin "S") (pinfunction "S_S") (pintype "passive"))
      (node (ref "R10") (pin "2") (pinfunction "2_2") (pintype "passive"))
      (node (ref "R11") (pin "1") (pinfunction "1_1") (pintype "passive"))
      (node (ref "R12") (pin "1") (pinfunction "1_1") (pintype "passive"))
      (node (ref "R13") (pin "1") (pinfunction "1_1") (pintype "passive"))
      (node (ref "R22") (pin "1") (pinfunction "1_1") (pintype "passive"))
      (node (ref "R23") (pin "1") (pinfunction "1_1") (pintype "passive"))
      (node (ref "R25") (pin "1") (pinfunction "1_1") (pintype "passive"))
      (node (ref "R6") (pin "1") (pinfunction "1_1") (pintype "passive"))
      (node (ref "R7") (pin "1") (pinfunction "1_1") (pintype "passive"))
      (node (ref "U$1") (pin "4A") (pinfunction "BAT_24V_-_4A") (pintype "power_in"))
      (node (ref "U$1") (pin "4B") (pinfunction "BAT_24V_-_4B") (pintype "power_in"))
      (node (ref "X1") (pin "3") (pinfunction "S_3") (pintype "passive"))
      (node (ref "X2") (pin "1") (pinfunction "KL_1") (pintype "passive"))
    )
    (net (code "14") (name "IN_L") (class "Default")
      (node (ref "IC2") (pin "1") (pinfunction "IN_1") (pintype "input"))
      (node (ref "IC4") (pin "4") (pinfunction "O_4") (pintype "output"))
    )
    (net (code "15") (name "IN_L_INVD") (class "Default")
      (node (ref "IC3") (pin "1") (pinfunction "IN_1") (pintype "input"))
      (node (ref "IC4") (pin "11") (pinfunction "O_11") (pintype "output"))
    )
    (net (code "16") (name "IN_R") (class "Default")
      (node (ref "IC4") (pin "3") (pinfunction "O_3") (pintype "output"))
      (node (ref "IC7") (pin "1") (pinfunction "IN_1") (pintype "input"))
    )
    (net (code "17") (name "IN_R_INVD") (class "Default")
      (node (ref "IC4") (pin "10") (pinfunction "O_10") (pintype "output"))
      (node (ref "IC8") (pin "1") (pinfunction "IN_1") (pintype "input"))
    )
    (net (code "18") (name "MOTOR_L_+") (class "Default")
      (node (ref "C2") (pin "-") (pinfunction "-_-") (pintype "passive"))
      (node (ref "D3") (pin "A") (pinfunction "A_A") (pintype "passive"))
      (node (ref "IC2") (pin "6") (pinfunction "VS_6") (pintype "power_in"))
      (node (ref "Q1") (pin "S") (pinfunction "S_S") (pintype "passive"))
      (node (ref "Q3") (pin "D") (pinfunction "D_D") (pintype "passive"))
      (node (ref "R8") (pin "1") (pinfunction "1_1") (pintype "passive"))
      (node (ref "U$1") (pin "5A") (pinfunction "MOTOR_L_+_5A") (pintype "power_in"))
      (node (ref "U$1") (pin "5B") (pinfunction "MOTOR_L_+_5B") (pintype "power_in"))
    )
    (net (code "19") (name "MOTOR_L_-") (class "Default")
      (node (ref "C3") (pin "-") (pinfunction "-_-") (pintype "passive"))
      (node (ref "D6") (pin "A") (pinfunction "A_A") (pintype "passive"))
      (node (ref "IC3") (pin "6") (pinfunction "VS_6") (pintype "power_in"))
      (node (ref "Q2") (pin "S") (pinfunction "S_S") (pintype "passive"))
      (node (ref "Q4") (pin "D") (pinfunction "D_D") (pintype "passive"))
      (node (ref "R5") (pin "1") (pinfunction "1_1") (pintype "passive"))
      (node (ref "U$1") (pin "6A") (pinfunction "MOTOR_L_-_6A") (pintype "power_in"))
      (node (ref "U$1") (pin "6B") (pinfunction "MOTOR_L_-_6B") (pintype "power_in"))
    )
    (net (code "20") (name "MOTOR_PWM_L") (class "Default")
      (node (ref "IC4") (pin "13") (pinfunction "I1_13") (pintype "input"))
      (node (ref "IC4") (pin "6") (pinfunction "I1_6") (pintype "input"))
      (node (ref "X1") (pin "2") (pinfunction "S_2") (pintype "passive"))
    )
    (net (code "21") (name "MOTOR_PWM_R") (class "Default")
      (node (ref "IC4") (pin "2") (pinfunction "I1_2") (pintype "input"))
      (node (ref "IC4") (pin "9") (pinfunction "I1_9") (pintype "input"))
      (node (ref "X1") (pin "4") (pinfunction "S_4") (pintype "passive"))
    )
    (net (code "22") (name "MOTOR_R_+") (class "Default")
      (node (ref "C12") (pin "-") (pinfunction "-_-") (pintype "passive"))
      (node (ref "D15") (pin "A") (pinfunction "A_A") (pintype "passive"))
      (node (ref "IC7") (pin "6") (pinfunction "VS_6") (pintype "power_in"))
      (node (ref "Q10") (pin "D") (pinfunction "D_D") (pintype "passive"))
      (node (ref "Q9") (pin "S") (pinfunction "S_S") (pintype "passive"))
      (node (ref "R24") (pin "1") (pinfunction "1_1") (pintype "passive"))
      (node (ref "U$1") (pin "2A") (pinfunction "MOTOR_R_+_2A") (pintype "power_in"))
      (node (ref "U$1") (pin "2B") (pinfunction "MOTOR_R_+_2B") (pintype "power_in"))
    )
    (net (code "23") (name "MOTOR_R_-") (class "Default")
      (node (ref "C13") (pin "-") (pinfunction "-_-") (pintype "passive"))
      (node (ref "D18") (pin "A") (pinfunction "A_A") (pintype "passive"))
      (node (ref "IC8") (pin "6") (pinfunction "VS_6") (pintype "power_in"))
      (node (ref "Q11") (pin "S") (pinfunction "S_S") (pintype "passive"))
      (node (ref "Q12") (pin "D") (pinfunction "D_D") (pintype "passive"))
      (node (ref "R21") (pin "1") (pinfunction "1_1") (pintype "passive"))
      (node (ref "U$1") (pin "1A") (pinfunction "MOTOR_R_-_1A") (pintype "power_in"))
      (node (ref "U$1") (pin "1B") (pinfunction "MOTOR_R_-_1B") (pintype "power_in"))
    )
    (net (code "24") (name "Net-(D3-PadC)") (class "Default")
      (node (ref "D3") (pin "C") (pinfunction "C_C") (pintype "passive"))
      (node (ref "Q1") (pin "G") (pinfunction "G_G") (pintype "passive"))
      (node (ref "R1") (pin "2") (pinfunction "2_2") (pintype "passive"))
      (node (ref "R8") (pin "2") (pinfunction "2_2") (pintype "passive"))
    )
    (net (code "25") (name "Net-(D4-PadC)") (class "Default")
      (node (ref "D4") (pin "C") (pinfunction "C_C") (pintype "passive"))
      (node (ref "Q3") (pin "G") (pinfunction "G_G") (pintype "passive"))
      (node (ref "R2") (pin "2") (pinfunction "2_2") (pintype "passive"))
      (node (ref "R7") (pin "2") (pinfunction "2_2") (pintype "passive"))
    )
    (net (code "26") (name "Net-(D5-PadC)") (class "Default")
      (node (ref "D5") (pin "C") (pinfunction "C_C") (pintype "passive"))
      (node (ref "Q4") (pin "G") (pinfunction "G_G") (pintype "passive"))
      (node (ref "R3") (pin "1") (pinfunction "1_1") (pintype "passive"))
      (node (ref "R6") (pin "2") (pinfunction "2_2") (pintype "passive"))
    )
    (net (code "27") (name "Net-(D6-PadC)") (class "Default")
      (node (ref "D6") (pin "C") (pinfunction "C_C") (pintype "passive"))
      (node (ref "Q2") (pin "G") (pinfunction "G_G") (pintype "passive"))
      (node (ref "R4") (pin "1") (pinfunction "1_1") (pintype "passive"))
      (node (ref "R5") (pin "2") (pinfunction "2_2") (pintype "passive"))
    )
    (net (code "28") (name "Net-(D15-PadC)") (class "Default")
      (node (ref "D15") (pin "C") (pinfunction "C_C") (pintype "passive"))
      (node (ref "Q9") (pin "G") (pinfunction "G_G") (pintype "passive"))
      (node (ref "R17") (pin "2") (pinfunction "2_2") (pintype "passive"))
      (node (ref "R24") (pin "2") (pinfunction "2_2") (pintype "passive"))
    )
    (net (code "29") (name "Net-(D16-PadC)") (class "Default")
      (node (ref "D16") (pin "C") (pinfunction "C_C") (pintype "passive"))
      (node (ref "Q10") (pin "G") (pinfunction "G_G") (pintype "passive"))
      (node (ref "R18") (pin "2") (pinfunction "2_2") (pintype "passive"))
      (node (ref "R23") (pin "2") (pinfunction "2_2") (pintype "passive"))
    )
    (net (code "30") (name "Net-(D17-PadC)") (class "Default")
      (node (ref "D17") (pin "C") (pinfunction "C_C") (pintype "passive"))
      (node (ref "Q12") (pin "G") (pinfunction "G_G") (pintype "passive"))
      (node (ref "R19") (pin "1") (pinfunction "1_1") (pintype "passive"))
      (node (ref "R22") (pin "2") (pinfunction "2_2") (pintype "passive"))
    )
    (net (code "31") (name "Net-(D18-PadC)") (class "Default")
      (node (ref "D18") (pin "C") (pinfunction "C_C") (pintype "passive"))
      (node (ref "Q11") (pin "G") (pinfunction "G_G") (pintype "passive"))
      (node (ref "R20") (pin "1") (pinfunction "1_1") (pintype "passive"))
      (node (ref "R21") (pin "2") (pinfunction "2_2") (pintype "passive"))
    )
    (net (code "32") (name "Net-(IC2-HO)") (class "Default")
      (node (ref "IC2") (pin "7") (pinfunction "HO_7") (pintype "output"))
      (node (ref "R1") (pin "1") (pinfunction "1_1") (pintype "passive"))
    )
    (net (code "33") (name "Net-(IC2-LO)") (class "Default")
      (node (ref "IC2") (pin "4") (pinfunction "LO_4") (pintype "output"))
      (node (ref "R2") (pin "1") (pinfunction "1_1") (pintype "passive"))
    )
    (net (code "34") (name "Net-(IC3-HO)") (class "Default")
      (node (ref "IC3") (pin "7") (pinfunction "HO_7") (pintype "output"))
      (node (ref "R4") (pin "2") (pinfunction "2_2") (pintype "passive"))
    )
    (net (code "35") (name "Net-(IC3-LO)") (class "Default")
      (node (ref "IC3") (pin "4") (pinfunction "LO_4") (pintype "output"))
      (node (ref "R3") (pin "2") (pinfunction "2_2") (pintype "passive"))
    )
    (net (code "36") (name "Net-(IC7-HO)") (class "Default")
      (node (ref "IC7") (pin "7") (pinfunction "HO_7") (pintype "output"))
      (node (ref "R17") (pin "1") (pinfunction "1_1") (pintype "passive"))
    )
    (net (code "37") (name "Net-(IC7-LO)") (class "Default")
      (node (ref "IC7") (pin "4") (pinfunction "LO_4") (pintype "output"))
      (node (ref "R18") (pin "1") (pinfunction "1_1") (pintype "passive"))
    )
    (net (code "38") (name "Net-(IC8-HO)") (class "Default")
      (node (ref "IC8") (pin "7") (pinfunction "HO_7") (pintype "output"))
      (node (ref "R20") (pin "2") (pinfunction "2_2") (pintype "passive"))
    )
    (net (code "39") (name "Net-(IC8-LO)") (class "Default")
      (node (ref "IC8") (pin "4") (pinfunction "LO_4") (pintype "output"))
      (node (ref "R19") (pin "2") (pinfunction "2_2") (pintype "passive"))
    )
    (net (code "40") (name "Net-(IC10-+V_OUT)") (class "Default")
      (node (ref "D8") (pin "C") (pinfunction "C_C") (pintype "passive"))
      (node (ref "IC10") (pin "P$2") (pinfunction "+V_OUT_P$2") (pintype "output"))
      (node (ref "L2") (pin "1") (pinfunction "1_1") (pintype "passive"))
    )
    (net (code "41") (name "Net-(IC11-+V_OUT)") (class "Default")
      (node (ref "D7") (pin "C") (pinfunction "C_C") (pintype "passive"))
      (node (ref "IC11") (pin "P$2") (pinfunction "+V_OUT_P$2") (pintype "output"))
      (node (ref "L1") (pin "1") (pinfunction "1_1") (pintype "passive"))
    )
    (net (code "42") (name "Net-(LED1-PadA)") (class "Default")
      (node (ref "LED1") (pin "A") (pinfunction "A_A") (pintype "passive"))
      (node (ref "R14") (pin "1") (pinfunction "1_1") (pintype "passive"))
    )
    (net (code "43") (name "Net-(LED2-PadA)") (class "Default")
      (node (ref "LED2") (pin "A") (pinfunction "A_A") (pintype "passive"))
      (node (ref "R15") (pin "2") (pinfunction "2_2") (pintype "passive"))
    )
    (net (code "44") (name "RESET") (class "Default")
      (node (ref "C16") (pin "1") (pinfunction "1_1") (pintype "passive"))
      (node (ref "IC9") (pin "1") (pinfunction "PB5/PCINT5/~{RESET}/ADC0/DW_1") (pintype "bidirectional"))
      (node (ref "R9") (pin "2") (pinfunction "2_2") (pintype "passive"))
    )
    (net (code "45") (name "VB1") (class "Default")
      (node (ref "C2") (pin "+") (pinfunction "+_+") (pintype "passive"))
      (node (ref "D1") (pin "C") (pinfunction "C_C") (pintype "passive"))
      (node (ref "IC2") (pin "8") (pinfunction "VB_8") (pintype "power_in"))
    )
    (net (code "46") (name "VB2") (class "Default")
      (node (ref "C3") (pin "+") (pinfunction "+_+") (pintype "passive"))
      (node (ref "D2") (pin "C") (pinfunction "C_C") (pintype "passive"))
      (node (ref "IC3") (pin "8") (pinfunction "VB_8") (pintype "power_in"))
    )
    (net (code "47") (name "VB3") (class "Default")
      (node (ref "C12") (pin "+") (pinfunction "+_+") (pintype "passive"))
      (node (ref "D13") (pin "C") (pinfunction "C_C") (pintype "passive"))
      (node (ref "IC7") (pin "8") (pinfunction "VB_8") (pintype "power_in"))
    )
    (net (code "48") (name "VB4") (class "Default")
      (node (ref "C13") (pin "+") (pinfunction "+_+") (pintype "passive"))
      (node (ref "D14") (pin "C") (pinfunction "C_C") (pintype "passive"))
      (node (ref "IC8") (pin "8") (pinfunction "VB_8") (pintype "power_in"))
    )
    (net (code "49") (name "unconnected-(IC5C-I-Pad5)") (class "Default")
      (node (ref "IC5") (pin "5") (pinfunction "I_5") (pintype "input"))
    )
    (net (code "50") (name "unconnected-(IC5C-O-Pad6)") (class "Default")
      (node (ref "IC5") (pin "6") (pinfunction "O_6") (pintype "output"))
    )
    (net (code "51") (name "unconnected-(IC5D-I-Pad9)") (class "Default")
      (node (ref "IC5") (pin "9") (pinfunction "I_9") (pintype "input"))
    )
    (net (code "52") (name "unconnected-(IC5D-O-Pad8)") (class "Default")
      (node (ref "IC5") (pin "8") (pinfunction "O_8") (pintype "output"))
    )
    (net (code "53") (name "unconnected-(IC5E-I-Pad11)") (class "Default")
      (node (ref "IC5") (pin "11") (pinfunction "I_11") (pintype "input"))
    )
    (net (code "54") (name "unconnected-(IC5E-O-Pad10)") (class "Default")
      (node (ref "IC5") (pin "10") (pinfunction "O_10") (pintype "output"))
    )
    (net (code "55") (name "unconnected-(IC5F-I-Pad13)") (class "Default")
      (node (ref "IC5") (pin "13") (pinfunction "I_13") (pintype "input"))
    )
    (net (code "56") (name "unconnected-(IC5F-O-Pad12)") (class "Default")
      (node (ref "IC5") (pin "12") (pinfunction "O_12") (pintype "output"))
    )
    (net (code "57") (name "unconnected-(IC9-PB1{slash}PCINT1{slash}AIN1{slash}OC0B{slash}INT0{slash}MISO-Pad6)") (class "Default")
      (node (ref "IC9") (pin "6") (pinfunction "PB1/PCINT1/AIN1/OC0B/INT0/MISO_6") (pintype "bidirectional"))
    )
    (net (code "58") (name "unconnected-(IC9-PB2{slash}PCINT2{slash}SCK{slash}ADC1{slash}T0-Pad7)") (class "Default")
      (node (ref "IC9") (pin "7") (pinfunction "PB2/PCINT2/SCK/ADC1/T0_7") (pintype "bidirectional"))
    )
    (net (code "59") (name "unconnected-(IC9-PB3{slash}PCINT3{slash}CLKI{slash}ADC3-Pad2)") (class "Default")
      (node (ref "IC9") (pin "2") (pinfunction "PB3/PCINT3/CLKI/ADC3_2") (pintype "bidirectional"))
    )
    (net (code "60") (name "unconnected-(R10-Pad1)") (class "Default")
      (node (ref "R10") (pin "1") (pinfunction "1_1") (pintype "passive"))
    )
  )
)
